# FA_2021_PCB.net
KiCad netlist of a schematic drawn in EAGLE
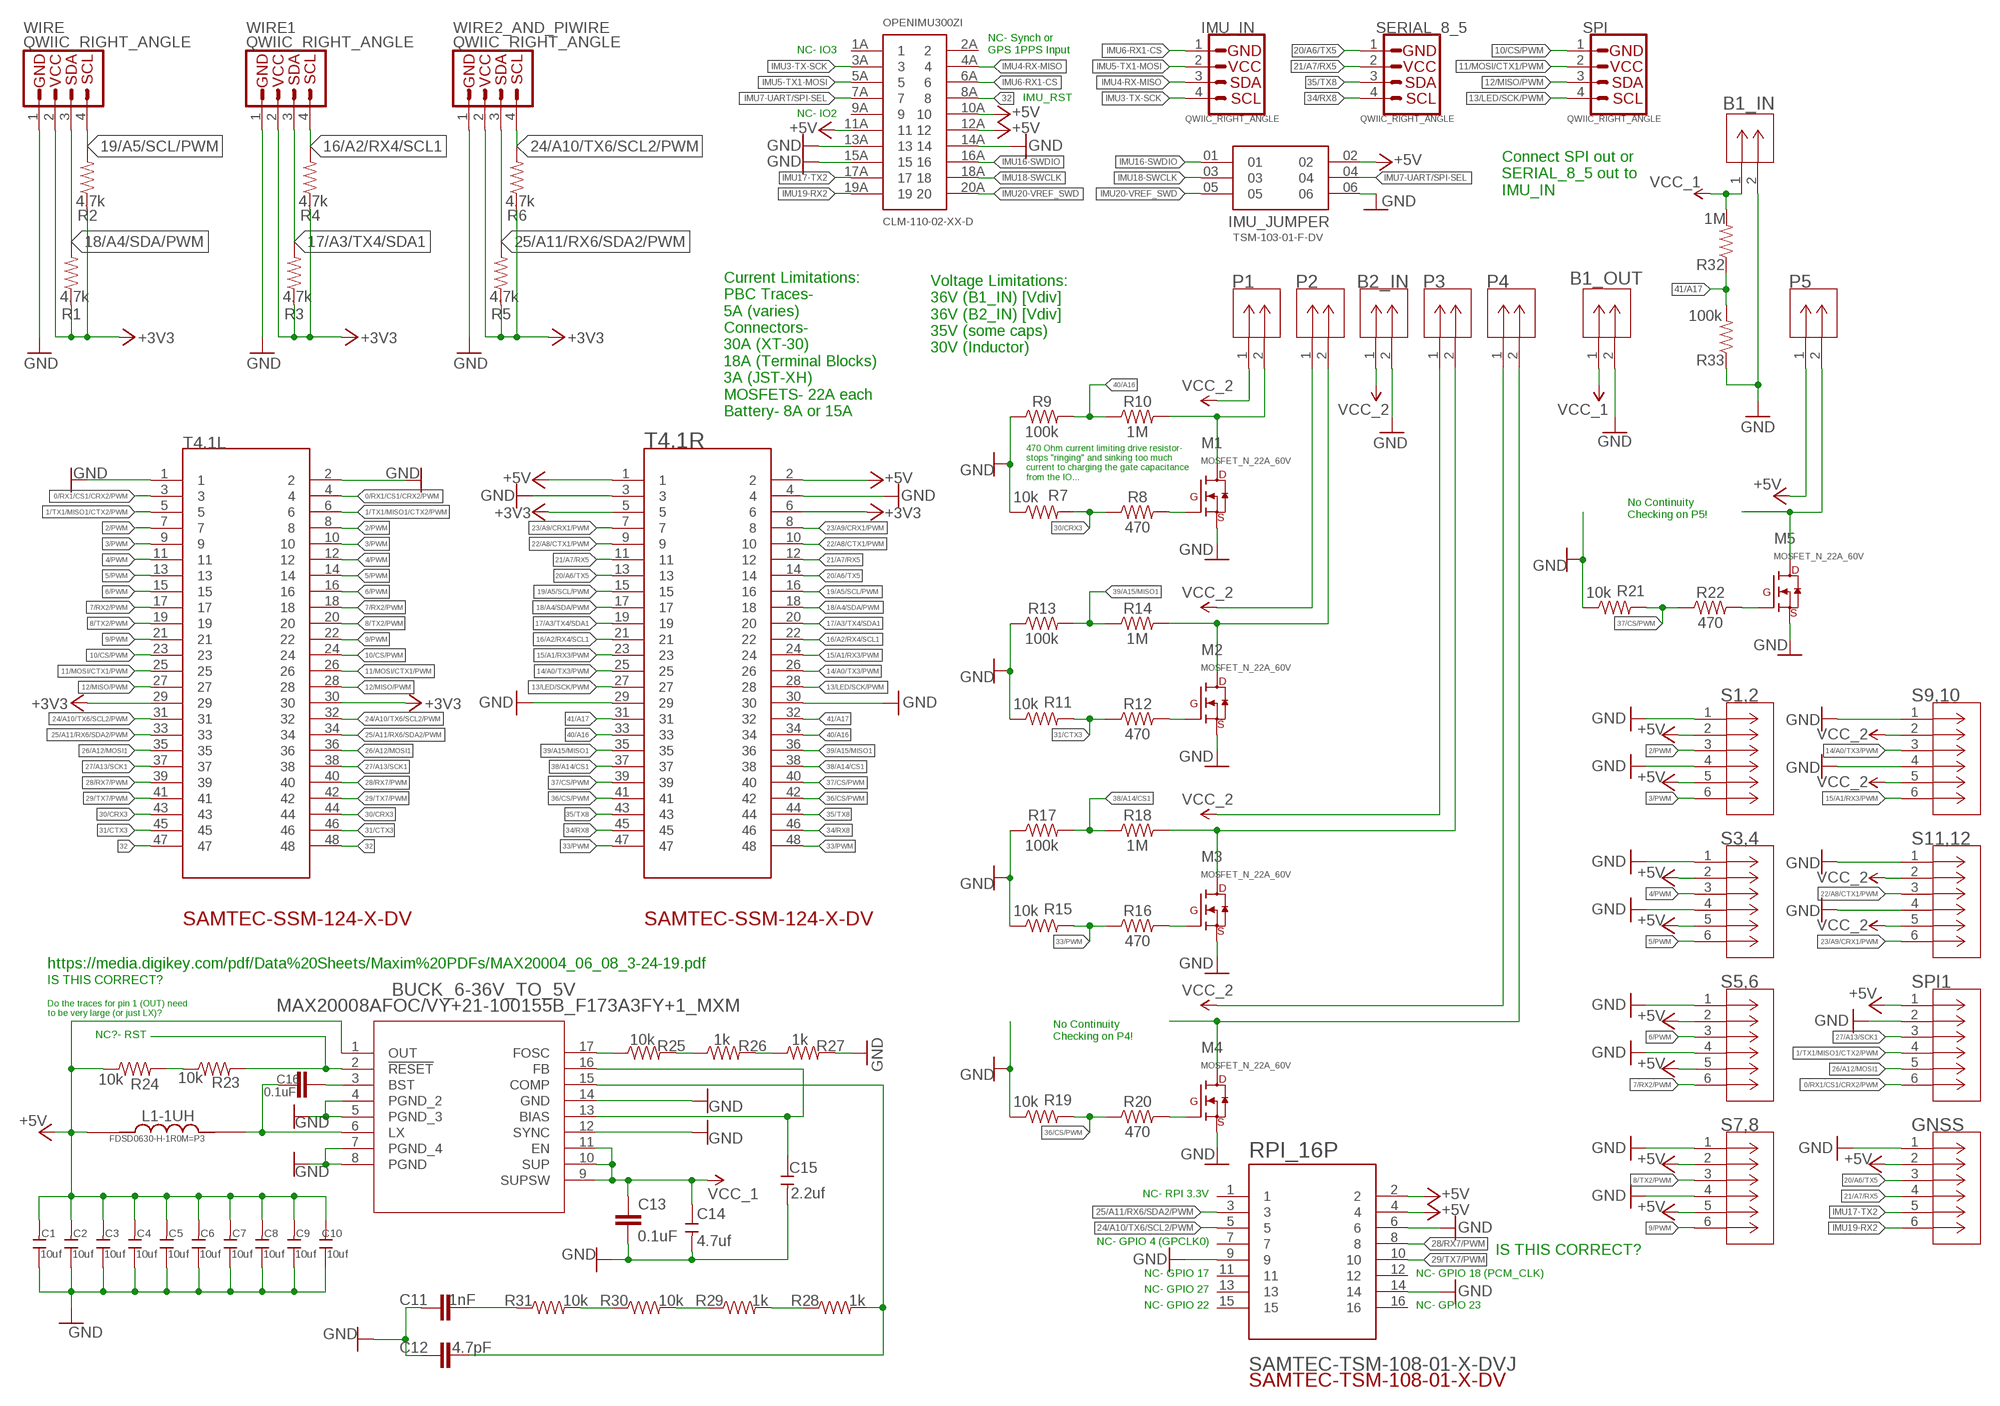
[diagram p0: schematic, sheet 1]

(export (version "E")
  (design (tool "Eeschema 10.0.6"))
  (components
    (comp (ref "B1_IN")
      (value "TERMINAL_BLOCK_2P_5MMCONN_1935161_PXC")
      (footprint "eagle-import:CONN_1935161_PXC")
      (fields
        (field (name "MANUFACTURER_PART_NUMBER") "1935161")
        (field (name "COPYRIGHT") "Copyright (C) 2018 Accelerated Designs. All rights reserved")
      )
      (libsource (lib "eagle-import") (part "TERMINAL_BLOCK_2P_5MMCONN_1935161_PXC"))
    )
    (comp (ref "B1_OUT")
      (value "TERMINAL_BLOCK_2P_5MMCONN_1935161_PXC")
      (footprint "eagle-import:CONN_1935161_PXC")
      (fields
        (field (name "MANUFACTURER_PART_NUMBER") "1935161")
        (field (name "COPYRIGHT") "Copyright (C) 2018 Accelerated Designs. All rights reserved")
      )
      (libsource (lib "eagle-import") (part "TERMINAL_BLOCK_2P_5MMCONN_1935161_PXC"))
    )
    (comp (ref "B2_IN")
      (value "TERMINAL_BLOCK_2P_5MMCONN_1935161_PXC")
      (footprint "eagle-import:CONN_1935161_PXC")
      (fields
        (field (name "MANUFACTURER_PART_NUMBER") "1935161")
        (field (name "COPYRIGHT") "Copyright (C) 2018 Accelerated Designs. All rights reserved")
      )
      (libsource (lib "eagle-import") (part "TERMINAL_BLOCK_2P_5MMCONN_1935161_PXC"))
    )
    (comp (ref "BUCK_6-36V_TO_5V")
      (value "MAX20008AFOC/VY+21-100155B_F173A3FY+1_MXM")
      (footprint "eagle-import:21-100155B_F173A3FY+1_MXM")
      (fields
        (field (name "MANUFACTURER_PART_NUMBER") "MAX20008AFOC/VY+")
        (field (name "COPYRIGHT") "Copyright (C) 2018 Accelerated Designs. All rights reserved")
      )
      (libsource (lib "eagle-import") (part "MAX20008AFOC/VY+21-100155B_F173A3FY+1_MXM"))
    )
    (comp (ref "C1")
      (value "10uf")
      (footprint "eagle-import:C1206")
      (fields (field (name "MPN") "CC1206KKX5R8BB106"))
      (libsource (lib "eagle-import") (part "CERAMIC-10UF-25V-10%-X5R(1206)"))
    )
    (comp (ref "C2")
      (value "10uf")
      (footprint "eagle-import:C1206")
      (fields (field (name "MPN") "CC1206KKX5R8BB106"))
      (libsource (lib "eagle-import") (part "CERAMIC-10UF-25V-10%-X5R(1206)"))
    )
    (comp (ref "C3")
      (value "10uf")
      (footprint "eagle-import:C1206")
      (fields (field (name "MPN") "CC1206KKX5R8BB106"))
      (libsource (lib "eagle-import") (part "CERAMIC-10UF-25V-10%-X5R(1206)"))
    )
    (comp (ref "C4")
      (value "10uf")
      (footprint "eagle-import:C1206")
      (fields (field (name "MPN") "CC1206KKX5R8BB106"))
      (libsource (lib "eagle-import") (part "CERAMIC-10UF-25V-10%-X5R(1206)"))
    )
    (comp (ref "C5")
      (value "10uf")
      (footprint "eagle-import:C1206")
      (fields (field (name "MPN") "CC1206KKX5R8BB106"))
      (libsource (lib "eagle-import") (part "CERAMIC-10UF-25V-10%-X5R(1206)"))
    )
    (comp (ref "C6")
      (value "10uf")
      (footprint "eagle-import:C1206")
      (fields (field (name "MPN") "CC1206KKX5R8BB106"))
      (libsource (lib "eagle-import") (part "CERAMIC-10UF-25V-10%-X5R(1206)"))
    )
    (comp (ref "C7")
      (value "10uf")
      (footprint "eagle-import:C1206")
      (fields (field (name "MPN") "CC1206KKX5R8BB106"))
      (libsource (lib "eagle-import") (part "CERAMIC-10UF-25V-10%-X5R(1206)"))
    )
    (comp (ref "C8")
      (value "10uf")
      (footprint "eagle-import:C1206")
      (fields (field (name "MPN") "CC1206KKX5R8BB106"))
      (libsource (lib "eagle-import") (part "CERAMIC-10UF-25V-10%-X5R(1206)"))
    )
    (comp (ref "C9")
      (value "10uf")
      (footprint "eagle-import:C1206")
      (fields (field (name "MPN") "CC1206KKX5R8BB106"))
      (libsource (lib "eagle-import") (part "CERAMIC-10UF-25V-10%-X5R(1206)"))
    )
    (comp (ref "C10")
      (value "10uf")
      (footprint "eagle-import:C1206")
      (fields (field (name "MPN") "CC1206KKX5R8BB106"))
      (libsource (lib "eagle-import") (part "CERAMIC-10UF-25V-10%-X5R(1206)"))
    )
    (comp (ref "C11")
      (value "1nF")
      (footprint "eagle-import:0603")
      (libsource (lib "eagle-import") (part "1.0NF/1000PF-0603-50V-10%"))
    )
    (comp (ref "C12")
      (value "4.7pF")
      (footprint "eagle-import:0603")
      (libsource (lib "eagle-import") (part "4.7PF-0603-50V-5%"))
    )
    (comp (ref "C13")
      (value "0.1uF")
      (footprint "eagle-import:0603")
      (libsource (lib "eagle-import") (part "0.1UF-0603-100V-10%"))
    )
    (comp (ref "C14")
      (value "4.7uf")
      (footprint "eagle-import:C0805")
      (fields (field (name "MPN") "CC0805KKX5R8BB475"))
      (libsource (lib "eagle-import") (part "CERAMIC-4.7UF-25V-10%-X5R(0805)"))
    )
    (comp (ref "C15")
      (value "2.2uf")
      (footprint "eagle-import:C0805")
      (fields (field (name "MPN") "CC0805KKX7R8BB225"))
      (libsource (lib "eagle-import") (part "CERAMIC-2.2UF-25V-10%-X7R(0805)"))
    )
    (comp (ref "C16")
      (value "0.1uF")
      (footprint "eagle-import:0603")
      (libsource (lib "eagle-import") (part "0.1UF-0603-100V-10%"))
    )
    (comp (ref "GNSS")
      (value "S6B-XH-SM4-TB(LF)(SN)CONN_S6B-XH-SM4-TB_JST")
      (footprint "eagle-import:CONN_S6B-XH-SM4-TB_JST")
      (fields
        (field (name "MANUFACTURER_PART_NUMBER") "S6B-XH-SM4-TB(LF)(SN)")
        (field (name "COPYRIGHT") "Copyright (C) 2018 Accelerated Designs. All rights reserved")
      )
      (libsource (lib "eagle-import") (part "S6B-XH-SM4-TB(LF)(SN)CONN_S6B-XH-SM4-TB_JST"))
    )
    (comp (ref "IMU_IN")
      (value "QWIIC_RIGHT_ANGLE")
      (footprint "eagle-import:JST04_1MM_RA")
      (libsource (lib "eagle-import") (part "QWIIC_CONNECTORJS-1MM"))
    )
    (comp (ref "IMU_JUMPER")
      (value "TSM-103-01-F-DV")
      (footprint "eagle-import:SAMTEC_TSM-103-01-F-DV")
      (fields (field (name "MANUFACTURER") "SAMTEC "))
      (libsource (lib "eagle-import") (part "TSM-103-01-F-DV"))
    )
    (comp (ref "L1-1UH")
      (value "FDSD0630-H-1R0M=P3")
      (footprint "eagle-import:IND_FDSD0630-H-1R0M=P3")
      (fields (field (name "DIGI-KEY_PART_NUMBER") "490-10878-1-ND") (field (name "MF") "Murata"))
      (libsource (lib "eagle-import") (part "FDSD0630-H-1R0M=P3"))
    )
    (comp (ref "M1")
      (value "MOSFET_N_22A_60V")
      (footprint "eagle-import:SOT-669_LFPAK56_POWERSO8")
      (libsource (lib "eagle-import") (part "MOSFET_N_22A_60V"))
    )
    (comp (ref "M2")
      (value "MOSFET_N_22A_60V")
      (footprint "eagle-import:SOT-669_LFPAK56_POWERSO8")
      (libsource (lib "eagle-import") (part "MOSFET_N_22A_60V"))
    )
    (comp (ref "M3")
      (value "MOSFET_N_22A_60V")
      (footprint "eagle-import:SOT-669_LFPAK56_POWERSO8")
      (libsource (lib "eagle-import") (part "MOSFET_N_22A_60V"))
    )
    (comp (ref "M4")
      (value "MOSFET_N_22A_60V")
      (footprint "eagle-import:SOT-669_LFPAK56_POWERSO8")
      (libsource (lib "eagle-import") (part "MOSFET_N_22A_60V"))
    )
    (comp (ref "M5")
      (value "MOSFET_N_22A_60V")
      (footprint "eagle-import:SOT-669_LFPAK56_POWERSO8")
      (libsource (lib "eagle-import") (part "MOSFET_N_22A_60V"))
    )
    (comp (ref "OPENIMU300ZI")
      (value "CLM-110-02-XX-D")
      (footprint "eagle-import:CLM-110-02-XX-D_MOD")
      (libsource (lib "eagle-import") (part "CLM-110-02-XX-D"))
    )
    (comp (ref "P1")
      (value "TERMINAL_BLOCK_2P_5MMCONN_1935161_PXC")
      (footprint "eagle-import:CONN_1935161_PXC")
      (fields
        (field (name "MANUFACTURER_PART_NUMBER") "1935161")
        (field (name "COPYRIGHT") "Copyright (C) 2018 Accelerated Designs. All rights reserved")
      )
      (libsource (lib "eagle-import") (part "TERMINAL_BLOCK_2P_5MMCONN_1935161_PXC"))
    )
    (comp (ref "P2")
      (value "TERMINAL_BLOCK_2P_5MMCONN_1935161_PXC")
      (footprint "eagle-import:CONN_1935161_PXC")
      (fields
        (field (name "MANUFACTURER_PART_NUMBER") "1935161")
        (field (name "COPYRIGHT") "Copyright (C) 2018 Accelerated Designs. All rights reserved")
      )
      (libsource (lib "eagle-import") (part "TERMINAL_BLOCK_2P_5MMCONN_1935161_PXC"))
    )
    (comp (ref "P3")
      (value "TERMINAL_BLOCK_2P_5MMCONN_1935161_PXC")
      (footprint "eagle-import:CONN_1935161_PXC")
      (fields
        (field (name "MANUFACTURER_PART_NUMBER") "1935161")
        (field (name "COPYRIGHT") "Copyright (C) 2018 Accelerated Designs. All rights reserved")
      )
      (libsource (lib "eagle-import") (part "TERMINAL_BLOCK_2P_5MMCONN_1935161_PXC"))
    )
    (comp (ref "P4")
      (value "TERMINAL_BLOCK_2P_5MMCONN_1935161_PXC")
      (footprint "eagle-import:CONN_1935161_PXC")
      (fields
        (field (name "MANUFACTURER_PART_NUMBER") "1935161")
        (field (name "COPYRIGHT") "Copyright (C) 2018 Accelerated Designs. All rights reserved")
      )
      (libsource (lib "eagle-import") (part "TERMINAL_BLOCK_2P_5MMCONN_1935161_PXC"))
    )
    (comp (ref "P5")
      (value "TERMINAL_BLOCK_2P_5MMCONN_1935161_PXC")
      (footprint "eagle-import:CONN_1935161_PXC")
      (fields
        (field (name "MANUFACTURER_PART_NUMBER") "1935161")
        (field (name "COPYRIGHT") "Copyright (C) 2018 Accelerated Designs. All rights reserved")
      )
      (libsource (lib "eagle-import") (part "TERMINAL_BLOCK_2P_5MMCONN_1935161_PXC"))
    )
    (comp (ref "R1")
      (value "4.7k")
      (footprint "eagle-import:0603")
      (libsource (lib "eagle-import") (part "4.7KOHM-0603-1/10W-1%"))
    )
    (comp (ref "R2")
      (value "4.7k")
      (footprint "eagle-import:0603")
      (libsource (lib "eagle-import") (part "4.7KOHM-0603-1/10W-1%"))
    )
    (comp (ref "R3")
      (value "4.7k")
      (footprint "eagle-import:0603")
      (libsource (lib "eagle-import") (part "4.7KOHM-0603-1/10W-1%"))
    )
    (comp (ref "R4")
      (value "4.7k")
      (footprint "eagle-import:0603")
      (libsource (lib "eagle-import") (part "4.7KOHM-0603-1/10W-1%"))
    )
    (comp (ref "R5")
      (value "4.7k")
      (footprint "eagle-import:0603")
      (libsource (lib "eagle-import") (part "4.7KOHM-0603-1/10W-1%"))
    )
    (comp (ref "R6")
      (value "4.7k")
      (footprint "eagle-import:0603")
      (libsource (lib "eagle-import") (part "4.7KOHM-0603-1/10W-1%"))
    )
    (comp (ref "R7")
      (value "10k")
      (footprint "eagle-import:0603")
      (libsource (lib "eagle-import") (part "10KOHM-0603-1/10W-1%"))
    )
    (comp (ref "R8")
      (value "470")
      (footprint "eagle-import:0603")
      (libsource (lib "eagle-import") (part "470OHM-0603-1/10W-1%"))
    )
    (comp (ref "R9")
      (value "100k")
      (footprint "eagle-import:0603")
      (libsource (lib "eagle-import") (part "100KOHM-0603-1/10W-1%"))
    )
    (comp (ref "R10")
      (value "1M")
      (footprint "eagle-import:0603")
      (libsource (lib "eagle-import") (part "1MOHM-0603-1/4W-5%"))
    )
    (comp (ref "R11")
      (value "10k")
      (footprint "eagle-import:0603")
      (libsource (lib "eagle-import") (part "10KOHM-0603-1/10W-1%"))
    )
    (comp (ref "R12")
      (value "470")
      (footprint "eagle-import:0603")
      (libsource (lib "eagle-import") (part "470OHM-0603-1/10W-1%"))
    )
    (comp (ref "R13")
      (value "100k")
      (footprint "eagle-import:0603")
      (libsource (lib "eagle-import") (part "100KOHM-0603-1/10W-1%"))
    )
    (comp (ref "R14")
      (value "1M")
      (footprint "eagle-import:0603")
      (libsource (lib "eagle-import") (part "1MOHM-0603-1/4W-5%"))
    )
    (comp (ref "R15")
      (value "10k")
      (footprint "eagle-import:0603")
      (libsource (lib "eagle-import") (part "10KOHM-0603-1/10W-1%"))
    )
    (comp (ref "R16")
      (value "470")
      (footprint "eagle-import:0603")
      (libsource (lib "eagle-import") (part "470OHM-0603-1/10W-1%"))
    )
    (comp (ref "R17")
      (value "100k")
      (footprint "eagle-import:0603")
      (libsource (lib "eagle-import") (part "100KOHM-0603-1/10W-1%"))
    )
    (comp (ref "R18")
      (value "1M")
      (footprint "eagle-import:0603")
      (libsource (lib "eagle-import") (part "1MOHM-0603-1/4W-5%"))
    )
    (comp (ref "R19")
      (value "10k")
      (footprint "eagle-import:0603")
      (libsource (lib "eagle-import") (part "10KOHM-0603-1/10W-1%"))
    )
    (comp (ref "R20")
      (value "470")
      (footprint "eagle-import:0603")
      (libsource (lib "eagle-import") (part "470OHM-0603-1/10W-1%"))
    )
    (comp (ref "R21")
      (value "10k")
      (footprint "eagle-import:0603")
      (libsource (lib "eagle-import") (part "10KOHM-0603-1/10W-1%"))
    )
    (comp (ref "R22")
      (value "470")
      (footprint "eagle-import:0603")
      (libsource (lib "eagle-import") (part "470OHM-0603-1/10W-1%"))
    )
    (comp (ref "R23")
      (value "10k")
      (footprint "eagle-import:0603")
      (libsource (lib "eagle-import") (part "10KOHM-0603-1/10W-1%"))
    )
    (comp (ref "R24")
      (value "10k")
      (footprint "eagle-import:0603")
      (libsource (lib "eagle-import") (part "10KOHM-0603-1/10W-1%"))
    )
    (comp (ref "R25")
      (value "10k")
      (footprint "eagle-import:0603")
      (libsource (lib "eagle-import") (part "10KOHM-0603-1/10W-1%"))
    )
    (comp (ref "R26")
      (value "1k")
      (footprint "eagle-import:0603")
      (libsource (lib "eagle-import") (part "1KOHM-0603-1/10W-1%"))
    )
    (comp (ref "R27")
      (value "1k")
      (footprint "eagle-import:0603")
      (libsource (lib "eagle-import") (part "1KOHM-0603-1/10W-1%"))
    )
    (comp (ref "R28")
      (value "1k")
      (footprint "eagle-import:0603")
      (libsource (lib "eagle-import") (part "1KOHM-0603-1/10W-1%"))
    )
    (comp (ref "R29")
      (value "1k")
      (footprint "eagle-import:0603")
      (libsource (lib "eagle-import") (part "1KOHM-0603-1/10W-1%"))
    )
    (comp (ref "R30")
      (value "10k")
      (footprint "eagle-import:0603")
      (libsource (lib "eagle-import") (part "10KOHM-0603-1/10W-1%"))
    )
    (comp (ref "R31")
      (value "10k")
      (footprint "eagle-import:0603")
      (libsource (lib "eagle-import") (part "10KOHM-0603-1/10W-1%"))
    )
    (comp (ref "R32")
      (value "1M")
      (footprint "eagle-import:0603")
      (libsource (lib "eagle-import") (part "1MOHM-0603-1/4W-5%"))
    )
    (comp (ref "R33")
      (value "100k")
      (footprint "eagle-import:0603")
      (libsource (lib "eagle-import") (part "100KOHM-0603-1/10W-1%"))
    )
    (comp (ref "RPI_16P")
      (value "SAMTEC-TSM-108-01-X-DVJ")
      (footprint "eagle-import:SAMTEC-TSM-108-01-X-DV")
      (fields (field (name "MF") "Samtec Inc.") (field (name "MP") "TSM-108-01-T-DV"))
      (libsource (lib "eagle-import") (part "SAMTEC-TSM-108-01-X-DVJ"))
    )
    (comp (ref "S1,2")
      (value "S6B-XH-SM4-TB(LF)(SN)CONN_S6B-XH-SM4-TB_JST")
      (footprint "eagle-import:CONN_S6B-XH-SM4-TB_JST")
      (fields
        (field (name "MANUFACTURER_PART_NUMBER") "S6B-XH-SM4-TB(LF)(SN)")
        (field (name "COPYRIGHT") "Copyright (C) 2018 Accelerated Designs. All rights reserved")
      )
      (libsource (lib "eagle-import") (part "S6B-XH-SM4-TB(LF)(SN)CONN_S6B-XH-SM4-TB_JST"))
    )
    (comp (ref "S3,4")
      (value "S6B-XH-SM4-TB(LF)(SN)CONN_S6B-XH-SM4-TB_JST")
      (footprint "eagle-import:CONN_S6B-XH-SM4-TB_JST")
      (fields
        (field (name "MANUFACTURER_PART_NUMBER") "S6B-XH-SM4-TB(LF)(SN)")
        (field (name "COPYRIGHT") "Copyright (C) 2018 Accelerated Designs. All rights reserved")
      )
      (libsource (lib "eagle-import") (part "S6B-XH-SM4-TB(LF)(SN)CONN_S6B-XH-SM4-TB_JST"))
    )
    (comp (ref "S5,6")
      (value "S6B-XH-SM4-TB(LF)(SN)CONN_S6B-XH-SM4-TB_JST")
      (footprint "eagle-import:CONN_S6B-XH-SM4-TB_JST")
      (fields
        (field (name "MANUFACTURER_PART_NUMBER") "S6B-XH-SM4-TB(LF)(SN)")
        (field (name "COPYRIGHT") "Copyright (C) 2018 Accelerated Designs. All rights reserved")
      )
      (libsource (lib "eagle-import") (part "S6B-XH-SM4-TB(LF)(SN)CONN_S6B-XH-SM4-TB_JST"))
    )
    (comp (ref "S7,8")
      (value "S6B-XH-SM4-TB(LF)(SN)CONN_S6B-XH-SM4-TB_JST")
      (footprint "eagle-import:CONN_S6B-XH-SM4-TB_JST")
      (fields
        (field (name "MANUFACTURER_PART_NUMBER") "S6B-XH-SM4-TB(LF)(SN)")
        (field (name "COPYRIGHT") "Copyright (C) 2018 Accelerated Designs. All rights reserved")
      )
      (libsource (lib "eagle-import") (part "S6B-XH-SM4-TB(LF)(SN)CONN_S6B-XH-SM4-TB_JST"))
    )
    (comp (ref "S9,10")
      (value "S6B-XH-SM4-TB(LF)(SN)CONN_S6B-XH-SM4-TB_JST")
      (footprint "eagle-import:CONN_S6B-XH-SM4-TB_JST")
      (fields
        (field (name "MANUFACTURER_PART_NUMBER") "S6B-XH-SM4-TB(LF)(SN)")
        (field (name "COPYRIGHT") "Copyright (C) 2018 Accelerated Designs. All rights reserved")
      )
      (libsource (lib "eagle-import") (part "S6B-XH-SM4-TB(LF)(SN)CONN_S6B-XH-SM4-TB_JST"))
    )
    (comp (ref "S11,12")
      (value "S6B-XH-SM4-TB(LF)(SN)CONN_S6B-XH-SM4-TB_JST")
      (footprint "eagle-import:CONN_S6B-XH-SM4-TB_JST")
      (fields
        (field (name "MANUFACTURER_PART_NUMBER") "S6B-XH-SM4-TB(LF)(SN)")
        (field (name "COPYRIGHT") "Copyright (C) 2018 Accelerated Designs. All rights reserved")
      )
      (libsource (lib "eagle-import") (part "S6B-XH-SM4-TB(LF)(SN)CONN_S6B-XH-SM4-TB_JST"))
    )
    (comp (ref "SERIAL_8_5")
      (value "QWIIC_RIGHT_ANGLE")
      (footprint "eagle-import:JST04_1MM_RA")
      (libsource (lib "eagle-import") (part "QWIIC_CONNECTORJS-1MM"))
    )
    (comp (ref "SPI")
      (value "QWIIC_RIGHT_ANGLE")
      (footprint "eagle-import:JST04_1MM_RA")
      (libsource (lib "eagle-import") (part "QWIIC_CONNECTORJS-1MM"))
    )
    (comp (ref "SPI1")
      (value "S6B-XH-SM4-TB(LF)(SN)CONN_S6B-XH-SM4-TB_JST")
      (footprint "eagle-import:CONN_S6B-XH-SM4-TB_JST")
      (fields
        (field (name "MANUFACTURER_PART_NUMBER") "S6B-XH-SM4-TB(LF)(SN)")
        (field (name "COPYRIGHT") "Copyright (C) 2018 Accelerated Designs. All rights reserved")
      )
      (libsource (lib "eagle-import") (part "S6B-XH-SM4-TB(LF)(SN)CONN_S6B-XH-SM4-TB_JST"))
    )
    (comp (ref "T4.1L")
      (value "SAMTEC-SSM-124-X-DVJ")
      (footprint "eagle-import:SAMTEC-SSM-124-X-DV")
      (libsource (lib "eagle-import") (part "SAMTEC-SSM-124-X-DVJ"))
    )
    (comp (ref "T4.1R")
      (value "SAMTEC-SSM-124-X-DVJ")
      (footprint "eagle-import:SAMTEC-SSM-124-X-DV")
      (libsource (lib "eagle-import") (part "SAMTEC-SSM-124-X-DVJ"))
    )
    (comp (ref "WIRE")
      (value "QWIIC_RIGHT_ANGLE")
      (footprint "eagle-import:JST04_1MM_RA")
      (libsource (lib "eagle-import") (part "QWIIC_CONNECTORJS-1MM"))
    )
    (comp (ref "WIRE1")
      (value "QWIIC_RIGHT_ANGLE")
      (footprint "eagle-import:JST04_1MM_RA")
      (libsource (lib "eagle-import") (part "QWIIC_CONNECTORJS-1MM"))
    )
    (comp (ref "WIRE2_AND_PIWIRE")
      (value "QWIIC_RIGHT_ANGLE")
      (footprint "eagle-import:JST04_1MM_RA")
      (libsource (lib "eagle-import") (part "QWIIC_CONNECTORJS-1MM"))
    )
  )
  (nets
    (net (code "1") (name "+3V3") (class "Default")
      (node (ref "R1") (pin "1") (pinfunction "1_1") (pintype "passive"))
      (node (ref "R2") (pin "1") (pinfunction "1_1") (pintype "passive"))
      (node (ref "R3") (pin "1") (pinfunction "1_1") (pintype "passive"))
      (node (ref "R4") (pin "1") (pinfunction "1_1") (pintype "passive"))
      (node (ref "R5") (pin "1") (pinfunction "1_1") (pintype "passive"))
      (node (ref "R6") (pin "1") (pinfunction "1_1") (pintype "passive"))
      (node (ref "T4.1L") (pin "29") (pinfunction "29_29") (pintype "passive"))
      (node (ref "T4.1L") (pin "30") (pinfunction "30_30") (pintype "passive"))
      (node (ref "T4.1R") (pin "5") (pinfunction "5_5") (pintype "passive"))
      (node (ref "T4.1R") (pin "6") (pinfunction "6_6") (pintype "passive"))
      (node (ref "WIRE") (pin "2") (pinfunction "2_2") (pintype "power_in"))
      (node (ref "WIRE1") (pin "2") (pinfunction "2_2") (pintype "power_in"))
      (node (ref "WIRE2_AND_PIWIRE") (pin "2") (pinfunction "2_2") (pintype "power_in"))
    )
    (net (code "2") (name "+5V") (class "Default")
      (node (ref "BUCK_6-36V_TO_5V") (pin "1") (pinfunction "OUT_1") (pintype "output"))
      (node (ref "C1") (pin "2") (pinfunction "2_2") (pintype "passive"))
      (node (ref "C10") (pin "2") (pinfunction "2_2") (pintype "passive"))
      (node (ref "C2") (pin "2") (pinfunction "2_2") (pintype "passive"))
      (node (ref "C3") (pin "2") (pinfunction "2_2") (pintype "passive"))
      (node (ref "C4") (pin "2") (pinfunction "2_2") (pintype "passive"))
      (node (ref "C5") (pin "2") (pinfunction "2_2") (pintype "passive"))
      (node (ref "C6") (pin "2") (pinfunction "2_2") (pintype "passive"))
      (node (ref "C7") (pin "2") (pinfunction "2_2") (pintype "passive"))
      (node (ref "C8") (pin "2") (pinfunction "2_2") (pintype "passive"))
      (node (ref "C9") (pin "2") (pinfunction "2_2") (pintype "passive"))
      (node (ref "GNSS") (pin "2") (pinfunction "2_2") (pintype "passive"))
      (node (ref "IMU_JUMPER") (pin "02") (pinfunction "02_02") (pintype "passive"))
      (node (ref "L1-1UH") (pin "1") (pinfunction "1_1") (pintype "passive"))
      (node (ref "OPENIMU300ZI") (pin "10A") (pinfunction "10_10A") (pintype "bidirectional"))
      (node (ref "OPENIMU300ZI") (pin "11A") (pinfunction "11_11A") (pintype "bidirectional"))
      (node (ref "OPENIMU300ZI") (pin "12A") (pinfunction "12_12A") (pintype "bidirectional"))
      (node (ref "P5") (pin "1") (pinfunction "1_1") (pintype "passive"))
      (node (ref "R24") (pin "1") (pinfunction "1_1") (pintype "passive"))
      (node (ref "RPI_16P") (pin "2") (pinfunction "2_2") (pintype "passive"))
      (node (ref "RPI_16P") (pin "4") (pinfunction "4_4") (pintype "passive"))
      (node (ref "S1,2") (pin "2") (pinfunction "2_2") (pintype "passive"))
      (node (ref "S1,2") (pin "5") (pinfunction "5_5") (pintype "passive"))
      (node (ref "S3,4") (pin "2") (pinfunction "2_2") (pintype "passive"))
      (node (ref "S3,4") (pin "5") (pinfunction "5_5") (pintype "passive"))
      (node (ref "S5,6") (pin "2") (pinfunction "2_2") (pintype "passive"))
      (node (ref "S5,6") (pin "5") (pinfunction "5_5") (pintype "passive"))
      (node (ref "S7,8") (pin "2") (pinfunction "2_2") (pintype "passive"))
      (node (ref "S7,8") (pin "5") (pinfunction "5_5") (pintype "passive"))
      (node (ref "SPI1") (pin "1") (pinfunction "1_1") (pintype "passive"))
      (node (ref "T4.1R") (pin "1") (pinfunction "1_1") (pintype "passive"))
      (node (ref "T4.1R") (pin "2") (pinfunction "2_2") (pintype "passive"))
    )
    (net (code "3") (name "0{slash}RX1{slash}CS1{slash}CRX2{slash}PWM") (class "Default")
      (node (ref "SPI1") (pin "6") (pinfunction "6_6") (pintype "passive"))
      (node (ref "T4.1L") (pin "3") (pinfunction "3_3") (pintype "passive"))
      (node (ref "T4.1L") (pin "4") (pinfunction "4_4") (pintype "passive"))
    )
    (net (code "4") (name "1{slash}TX1{slash}MISO1{slash}CTX2{slash}PWM") (class "Default")
      (node (ref "SPI1") (pin "4") (pinfunction "4_4") (pintype "passive"))
      (node (ref "T4.1L") (pin "5") (pinfunction "5_5") (pintype "passive"))
      (node (ref "T4.1L") (pin "6") (pinfunction "6_6") (pintype "passive"))
    )
    (net (code "5") (name "2{slash}PWM") (class "Default")
      (node (ref "S1,2") (pin "3") (pinfunction "3_3") (pintype "passive"))
      (node (ref "T4.1L") (pin "7") (pinfunction "7_7") (pintype "passive"))
      (node (ref "T4.1L") (pin "8") (pinfunction "8_8") (pintype "passive"))
    )
    (net (code "6") (name "3{slash}PWM") (class "Default")
      (node (ref "S1,2") (pin "6") (pinfunction "6_6") (pintype "passive"))
      (node (ref "T4.1L") (pin "10") (pinfunction "10_10") (pintype "passive"))
      (node (ref "T4.1L") (pin "9") (pinfunction "9_9") (pintype "passive"))
    )
    (net (code "7") (name "4{slash}PWM") (class "Default")
      (node (ref "S3,4") (pin "3") (pinfunction "3_3") (pintype "passive"))
      (node (ref "T4.1L") (pin "11") (pinfunction "11_11") (pintype "passive"))
      (node (ref "T4.1L") (pin "12") (pinfunction "12_12") (pintype "passive"))
    )
    (net (code "8") (name "5{slash}PWM") (class "Default")
      (node (ref "S3,4") (pin "6") (pinfunction "6_6") (pintype "passive"))
      (node (ref "T4.1L") (pin "13") (pinfunction "13_13") (pintype "passive"))
      (node (ref "T4.1L") (pin "14") (pinfunction "14_14") (pintype "passive"))
    )
    (net (code "9") (name "6{slash}PWM") (class "Default")
      (node (ref "S5,6") (pin "3") (pinfunction "3_3") (pintype "passive"))
      (node (ref "T4.1L") (pin "15") (pinfunction "15_15") (pintype "passive"))
      (node (ref "T4.1L") (pin "16") (pinfunction "16_16") (pintype "passive"))
    )
    (net (code "10") (name "7{slash}RX2{slash}PWM") (class "Default")
      (node (ref "S5,6") (pin "6") (pinfunction "6_6") (pintype "passive"))
      (node (ref "T4.1L") (pin "17") (pinfunction "17_17") (pintype "passive"))
      (node (ref "T4.1L") (pin "18") (pinfunction "18_18") (pintype "passive"))
    )
    (net (code "11") (name "8{slash}TX2{slash}PWM") (class "Default")
      (node (ref "S7,8") (pin "3") (pinfunction "3_3") (pintype "passive"))
      (node (ref "T4.1L") (pin "19") (pinfunction "19_19") (pintype "passive"))
      (node (ref "T4.1L") (pin "20") (pinfunction "20_20") (pintype "passive"))
    )
    (net (code "12") (name "9{slash}PWM") (class "Default")
      (node (ref "S7,8") (pin "6") (pinfunction "6_6") (pintype "passive"))
      (node (ref "T4.1L") (pin "21") (pinfunction "21_21") (pintype "passive"))
      (node (ref "T4.1L") (pin "22") (pinfunction "22_22") (pintype "passive"))
    )
    (net (code "13") (name "10{slash}CS{slash}PWM") (class "Default")
      (node (ref "SPI") (pin "1") (pinfunction "1_1") (pintype "power_in"))
      (node (ref "T4.1L") (pin "23") (pinfunction "23_23") (pintype "passive"))
      (node (ref "T4.1L") (pin "24") (pinfunction "24_24") (pintype "passive"))
    )
    (net (code "14") (name "11{slash}MOSI{slash}CTX1{slash}PWM") (class "Default")
      (node (ref "SPI") (pin "2") (pinfunction "2_2") (pintype "power_in"))
      (node (ref "T4.1L") (pin "25") (pinfunction "25_25") (pintype "passive"))
      (node (ref "T4.1L") (pin "26") (pinfunction "26_26") (pintype "passive"))
    )
    (net (code "15") (name "12{slash}MISO{slash}PWM") (class "Default")
      (node (ref "SPI") (pin "3") (pinfunction "3_3") (pintype "passive"))
      (node (ref "T4.1L") (pin "27") (pinfunction "27_27") (pintype "passive"))
      (node (ref "T4.1L") (pin "28") (pinfunction "28_28") (pintype "passive"))
    )
    (net (code "16") (name "13{slash}LED{slash}SCK{slash}PWM") (class "Default")
      (node (ref "SPI") (pin "4") (pinfunction "4_4") (pintype "passive"))
      (node (ref "T4.1R") (pin "27") (pinfunction "27_27") (pintype "passive"))
      (node (ref "T4.1R") (pin "28") (pinfunction "28_28") (pintype "passive"))
    )
    (net (code "17") (name "14{slash}A0{slash}TX3{slash}PWM") (class "Default")
      (node (ref "S9,10") (pin "3") (pinfunction "3_3") (pintype "passive"))
      (node (ref "T4.1R") (pin "25") (pinfunction "25_25") (pintype "passive"))
      (node (ref "T4.1R") (pin "26") (pinfunction "26_26") (pintype "passive"))
    )
    (net (code "18") (name "15{slash}A1{slash}RX3{slash}PWM") (class "Default")
      (node (ref "S9,10") (pin "6") (pinfunction "6_6") (pintype "passive"))
      (node (ref "T4.1R") (pin "23") (pinfunction "23_23") (pintype "passive"))
      (node (ref "T4.1R") (pin "24") (pinfunction "24_24") (pintype "passive"))
    )
    (net (code "19") (name "16{slash}A2{slash}RX4{slash}SCL1") (class "Default")
      (node (ref "R4") (pin "2") (pinfunction "2_2") (pintype "passive"))
      (node (ref "T4.1R") (pin "21") (pinfunction "21_21") (pintype "passive"))
      (node (ref "T4.1R") (pin "22") (pinfunction "22_22") (pintype "passive"))
      (node (ref "WIRE1") (pin "4") (pinfunction "4_4") (pintype "passive"))
    )
    (net (code "20") (name "17{slash}A3{slash}TX4{slash}SDA1") (class "Default")
      (node (ref "R3") (pin "2") (pinfunction "2_2") (pintype "passive"))
      (node (ref "T4.1R") (pin "19") (pinfunction "19_19") (pintype "passive"))
      (node (ref "T4.1R") (pin "20") (pinfunction "20_20") (pintype "passive"))
      (node (ref "WIRE1") (pin "3") (pinfunction "3_3") (pintype "passive"))
    )
    (net (code "21") (name "18{slash}A4{slash}SDA{slash}PWM") (class "Default")
      (node (ref "R1") (pin "2") (pinfunction "2_2") (pintype "passive"))
      (node (ref "T4.1R") (pin "17") (pinfunction "17_17") (pintype "passive"))
      (node (ref "T4.1R") (pin "18") (pinfunction "18_18") (pintype "passive"))
      (node (ref "WIRE") (pin "3") (pinfunction "3_3") (pintype "passive"))
    )
    (net (code "22") (name "19{slash}A5{slash}SCL{slash}PWM") (class "Default")
      (node (ref "R2") (pin "2") (pinfunction "2_2") (pintype "passive"))
      (node (ref "T4.1R") (pin "15") (pinfunction "15_15") (pintype "passive"))
      (node (ref "T4.1R") (pin "16") (pinfunction "16_16") (pintype "passive"))
      (node (ref "WIRE") (pin "4") (pinfunction "4_4") (pintype "passive"))
    )
    (net (code "23") (name "20{slash}A6{slash}TX5") (class "Default")
      (node (ref "GNSS") (pin "3") (pinfunction "3_3") (pintype "passive"))
      (node (ref "SERIAL_8_5") (pin "1") (pinfunction "1_1") (pintype "power_in"))
      (node (ref "T4.1R") (pin "13") (pinfunction "13_13") (pintype "passive"))
      (node (ref "T4.1R") (pin "14") (pinfunction "14_14") (pintype "passive"))
    )
    (net (code "24") (name "21{slash}A7{slash}RX5") (class "Default")
      (node (ref "GNSS") (pin "4") (pinfunction "4_4") (pintype "passive"))
      (node (ref "SERIAL_8_5") (pin "2") (pinfunction "2_2") (pintype "power_in"))
      (node (ref "T4.1R") (pin "11") (pinfunction "11_11") (pintype "passive"))
      (node (ref "T4.1R") (pin "12") (pinfunction "12_12") (pintype "passive"))
    )
    (net (code "25") (name "22{slash}A8{slash}CTX1{slash}PWM") (class "Default")
      (node (ref "S11,12") (pin "3") (pinfunction "3_3") (pintype "passive"))
      (node (ref "T4.1R") (pin "10") (pinfunction "10_10") (pintype "passive"))
      (node (ref "T4.1R") (pin "9") (pinfunction "9_9") (pintype "passive"))
    )
    (net (code "26") (name "23{slash}A9{slash}CRX1{slash}PWM") (class "Default")
      (node (ref "S11,12") (pin "6") (pinfunction "6_6") (pintype "passive"))
      (node (ref "T4.1R") (pin "7") (pinfunction "7_7") (pintype "passive"))
      (node (ref "T4.1R") (pin "8") (pinfunction "8_8") (pintype "passive"))
    )
    (net (code "27") (name "24{slash}A10{slash}TX6{slash}SCL2{slash}PWM") (class "Default")
      (node (ref "R6") (pin "2") (pinfunction "2_2") (pintype "passive"))
      (node (ref "RPI_16P") (pin "5") (pinfunction "5_5") (pintype "passive"))
      (node (ref "T4.1L") (pin "31") (pinfunction "31_31") (pintype "passive"))
      (node (ref "T4.1L") (pin "32") (pinfunction "32_32") (pintype "passive"))
      (node (ref "WIRE2_AND_PIWIRE") (pin "4") (pinfunction "4_4") (pintype "passive"))
    )
    (net (code "28") (name "25{slash}A11{slash}RX6{slash}SDA2{slash}PWM") (class "Default")
      (node (ref "R5") (pin "2") (pinfunction "2_2") (pintype "passive"))
      (node (ref "RPI_16P") (pin "3") (pinfunction "3_3") (pintype "passive"))
      (node (ref "T4.1L") (pin "33") (pinfunction "33_33") (pintype "passive"))
      (node (ref "T4.1L") (pin "34") (pinfunction "34_34") (pintype "passive"))
      (node (ref "WIRE2_AND_PIWIRE") (pin "3") (pinfunction "3_3") (pintype "passive"))
    )
    (net (code "29") (name "26{slash}A12{slash}MOSI1") (class "Default")
      (node (ref "SPI1") (pin "5") (pinfunction "5_5") (pintype "passive"))
      (node (ref "T4.1L") (pin "35") (pinfunction "35_35") (pintype "passive"))
      (node (ref "T4.1L") (pin "36") (pinfunction "36_36") (pintype "passive"))
    )
    (net (code "30") (name "27{slash}A13{slash}SCK1") (class "Default")
      (node (ref "SPI1") (pin "3") (pinfunction "3_3") (pintype "passive"))
      (node (ref "T4.1L") (pin "37") (pinfunction "37_37") (pintype "passive"))
      (node (ref "T4.1L") (pin "38") (pinfunction "38_38") (pintype "passive"))
    )
    (net (code "31") (name "28{slash}RX7{slash}PWM") (class "Default")
      (node (ref "RPI_16P") (pin "8") (pinfunction "8_8") (pintype "passive"))
      (node (ref "T4.1L") (pin "39") (pinfunction "39_39") (pintype "passive"))
      (node (ref "T4.1L") (pin "40") (pinfunction "40_40") (pintype "passive"))
    )
    (net (code "32") (name "29{slash}TX7{slash}PWM") (class "Default")
      (node (ref "RPI_16P") (pin "10") (pinfunction "10_10") (pintype "passive"))
      (node (ref "T4.1L") (pin "41") (pinfunction "41_41") (pintype "passive"))
      (node (ref "T4.1L") (pin "42") (pinfunction "42_42") (pintype "passive"))
    )
    (net (code "33") (name "30{slash}CRX3") (class "Default")
      (node (ref "R7") (pin "2") (pinfunction "2_2") (pintype "passive"))
      (node (ref "R8") (pin "1") (pinfunction "1_1") (pintype "passive"))
      (node (ref "T4.1L") (pin "43") (pinfunction "43_43") (pintype "passive"))
      (node (ref "T4.1L") (pin "44") (pinfunction "44_44") (pintype "passive"))
    )
    (net (code "34") (name "31{slash}CTX3") (class "Default")
      (node (ref "R11") (pin "2") (pinfunction "2_2") (pintype "passive"))
      (node (ref "R12") (pin "1") (pinfunction "1_1") (pintype "passive"))
      (node (ref "T4.1L") (pin "45") (pinfunction "45_45") (pintype "passive"))
      (node (ref "T4.1L") (pin "46") (pinfunction "46_46") (pintype "passive"))
    )
    (net (code "35") (name "32") (class "Default")
      (node (ref "OPENIMU300ZI") (pin "8A") (pinfunction "8_8A") (pintype "bidirectional"))
      (node (ref "T4.1L") (pin "47") (pinfunction "47_47") (pintype "passive"))
      (node (ref "T4.1L") (pin "48") (pinfunction "48_48") (pintype "passive"))
    )
    (net (code "36") (name "33{slash}PWM") (class "Default")
      (node (ref "R15") (pin "2") (pinfunction "2_2") (pintype "passive"))
      (node (ref "R16") (pin "1") (pinfunction "1_1") (pintype "passive"))
      (node (ref "T4.1R") (pin "47") (pinfunction "47_47") (pintype "passive"))
      (node (ref "T4.1R") (pin "48") (pinfunction "48_48") (pintype "passive"))
    )
    (net (code "37") (name "34{slash}RX8") (class "Default")
      (node (ref "SERIAL_8_5") (pin "4") (pinfunction "4_4") (pintype "passive"))
      (node (ref "T4.1R") (pin "45") (pinfunction "45_45") (pintype "passive"))
      (node (ref "T4.1R") (pin "46") (pinfunction "46_46") (pintype "passive"))
    )
    (net (code "38") (name "35{slash}TX8") (class "Default")
      (node (ref "SERIAL_8_5") (pin "3") (pinfunction "3_3") (pintype "passive"))
      (node (ref "T4.1R") (pin "43") (pinfunction "43_43") (pintype "passive"))
      (node (ref "T4.1R") (pin "44") (pinfunction "44_44") (pintype "passive"))
    )
    (net (code "39") (name "36{slash}CS{slash}PWM") (class "Default")
      (node (ref "R19") (pin "2") (pinfunction "2_2") (pintype "passive"))
      (node (ref "R20") (pin "1") (pinfunction "1_1") (pintype "passive"))
      (node (ref "T4.1R") (pin "41") (pinfunction "41_41") (pintype "passive"))
      (node (ref "T4.1R") (pin "42") (pinfunction "42_42") (pintype "passive"))
    )
    (net (code "40") (name "37{slash}CS{slash}PWM") (class "Default")
      (node (ref "R21") (pin "2") (pinfunction "2_2") (pintype "passive"))
      (node (ref "R22") (pin "1") (pinfunction "1_1") (pintype "passive"))
      (node (ref "T4.1R") (pin "39") (pinfunction "39_39") (pintype "passive"))
      (node (ref "T4.1R") (pin "40") (pinfunction "40_40") (pintype "passive"))
    )
    (net (code "41") (name "38{slash}A14{slash}CS1") (class "Default")
      (node (ref "R17") (pin "2") (pinfunction "2_2") (pintype "passive"))
      (node (ref "R18") (pin "1") (pinfunction "1_1") (pintype "passive"))
      (node (ref "T4.1R") (pin "37") (pinfunction "37_37") (pintype "passive"))
      (node (ref "T4.1R") (pin "38") (pinfunction "38_38") (pintype "passive"))
    )
    (net (code "42") (name "39{slash}A15{slash}MISO1") (class "Default")
      (node (ref "R13") (pin "2") (pinfunction "2_2") (pintype "passive"))
      (node (ref "R14") (pin "1") (pinfunction "1_1") (pintype "passive"))
      (node (ref "T4.1R") (pin "35") (pinfunction "35_35") (pintype "passive"))
      (node (ref "T4.1R") (pin "36") (pinfunction "36_36") (pintype "passive"))
    )
    (net (code "43") (name "40{slash}A16") (class "Default")
      (node (ref "R10") (pin "1") (pinfunction "1_1") (pintype "passive"))
      (node (ref "R9") (pin "2") (pinfunction "2_2") (pintype "passive"))
      (node (ref "T4.1R") (pin "33") (pinfunction "33_33") (pintype "passive"))
      (node (ref "T4.1R") (pin "34") (pinfunction "34_34") (pintype "passive"))
    )
    (net (code "44") (name "41{slash}A17") (class "Default")
      (node (ref "R32") (pin "1") (pinfunction "1_1") (pintype "passive"))
      (node (ref "R33") (pin "2") (pinfunction "2_2") (pintype "passive"))
      (node (ref "T4.1R") (pin "31") (pinfunction "31_31") (pintype "passive"))
      (node (ref "T4.1R") (pin "32") (pinfunction "32_32") (pintype "passive"))
    )
    (net (code "45") (name "GND") (class "Default")
      (node (ref "B1_IN") (pin "2") (pinfunction "2_2") (pintype "passive"))
      (node (ref "B1_OUT") (pin "2") (pinfunction "2_2") (pintype "passive"))
      (node (ref "B2_IN") (pin "2") (pinfunction "2_2") (pintype "passive"))
      (node (ref "BUCK_6-36V_TO_5V") (pin "12") (pinfunction "SYNC_12") (pintype "passive"))
      (node (ref "BUCK_6-36V_TO_5V") (pin "14") (pinfunction "GND_14") (pintype "power_in"))
      (node (ref "BUCK_6-36V_TO_5V") (pin "4") (pinfunction "PGND_2_4") (pintype "power_in"))
      (node (ref "BUCK_6-36V_TO_5V") (pin "5") (pinfunction "PGND_3_5") (pintype "power_in"))
      (node (ref "BUCK_6-36V_TO_5V") (pin "7") (pinfunction "PGND_4_7") (pintype "power_in"))
      (node (ref "BUCK_6-36V_TO_5V") (pin "8") (pinfunction "PGND_8") (pintype "power_in"))
      (node (ref "C1") (pin "1") (pinfunction "1_1") (pintype "passive"))
      (node (ref "C10") (pin "1") (pinfunction "1_1") (pintype "passive"))
      (node (ref "C11") (pin "1") (pinfunction "1_1") (pintype "passive"))
      (node (ref "C12") (pin "1") (pinfunction "1_1") (pintype "passive"))
      (node (ref "C13") (pin "2") (pinfunction "2_2") (pintype "passive"))
      (node (ref "C14") (pin "2") (pinfunction "2_2") (pintype "passive"))
      (node (ref "C15") (pin "2") (pinfunction "2_2") (pintype "passive"))
      (node (ref "C2") (pin "1") (pinfunction "1_1") (pintype "passive"))
      (node (ref "C3") (pin "1") (pinfunction "1_1") (pintype "passive"))
      (node (ref "C4") (pin "1") (pinfunction "1_1") (pintype "passive"))
      (node (ref "C5") (pin "1") (pinfunction "1_1") (pintype "passive"))
      (node (ref "C6") (pin "1") (pinfunction "1_1") (pintype "passive"))
      (node (ref "C7") (pin "1") (pinfunction "1_1") (pintype "passive"))
      (node (ref "C8") (pin "1") (pinfunction "1_1") (pintype "passive"))
      (node (ref "C9") (pin "1") (pinfunction "1_1") (pintype "passive"))
      (node (ref "GNSS") (pin "1") (pinfunction "1_1") (pintype "passive"))
      (node (ref "IMU_JUMPER") (pin "06") (pinfunction "06_06") (pintype "passive"))
      (node (ref "M1") (pin "1") (pinfunction "S_1") (pintype "passive"))
      (node (ref "M1") (pin "2") (pinfunction "S_2") (pintype "passive"))
      (node (ref "M1") (pin "3") (pinfunction "S_3") (pintype "passive"))
      (node (ref "M2") (pin "1") (pinfunction "S_1") (pintype "passive"))
      (node (ref "M2") (pin "2") (pinfunction "S_2") (pintype "passive"))
      (node (ref "M2") (pin "3") (pinfunction "S_3") (pintype "passive"))
      (node (ref "M3") (pin "1") (pinfunction "S_1") (pintype "passive"))
      (node (ref "M3") (pin "2") (pinfunction "S_2") (pintype "passive"))
      (node (ref "M3") (pin "3") (pinfunction "S_3") (pintype "passive"))
      (node (ref "M4") (pin "1") (pinfunction "S_1") (pintype "passive"))
      (node (ref "M4") (pin "2") (pinfunction "S_2") (pintype "passive"))
      (node (ref "M4") (pin "3") (pinfunction "S_3") (pintype "passive"))
      (node (ref "M5") (pin "1") (pinfunction "S_1") (pintype "passive"))
      (node (ref "M5") (pin "2") (pinfunction "S_2") (pintype "passive"))
      (node (ref "M5") (pin "3") (pinfunction "S_3") (pintype "passive"))
      (node (ref "OPENIMU300ZI") (pin "13A") (pinfunction "13_13A") (pintype "bidirectional"))
      (node (ref "OPENIMU300ZI") (pin "14A") (pinfunction "14_14A") (pintype "bidirectional"))
      (node (ref "OPENIMU300ZI") (pin "15A") (pinfunction "15_15A") (pintype "bidirectional"))
      (node (ref "R11") (pin "1") (pinfunction "1_1") (pintype "passive"))
      (node (ref "R13") (pin "1") (pinfunction "1_1") (pintype "passive"))
      (node (ref "R15") (pin "1") (pinfunction "1_1") (pintype "passive"))
      (node (ref "R17") (pin "1") (pinfunction "1_1") (pintype "passive"))
      (node (ref "R19") (pin "1") (pinfunction "1_1") (pintype "passive"))
      (node (ref "R21") (pin "1") (pinfunction "1_1") (pintype "passive"))
      (node (ref "R27") (pin "2") (pinfunction "2_2") (pintype "passive"))
      (node (ref "R33") (pin "1") (pinfunction "1_1") (pintype "passive"))
      (node (ref "R7") (pin "1") (pinfunction "1_1") (pintype "passive"))
      (node (ref "R9") (pin "1") (pinfunction "1_1") (pintype "passive"))
      (node (ref "RPI_16P") (pin "14") (pinfunction "14_14") (pintype "passive"))
      (node (ref "RPI_16P") (pin "6") (pinfunction "6_6") (pintype "passive"))
      (node (ref "RPI_16P") (pin "9") (pinfunction "9_9") (pintype "passive"))
      (node (ref "S1,2") (pin "1") (pinfunction "1_1") (pintype "passive"))
      (node (ref "S1,2") (pin "4") (pinfunction "4_4") (pintype "passive"))
      (node (ref "S11,12") (pin "1") (pinfunction "1_1") (pintype "passive"))
      (node (ref "S11,12") (pin "4") (pinfunction "4_4") (pintype "passive"))
      (node (ref "S3,4") (pin "1") (pinfunction "1_1") (pintype "passive"))
      (node (ref "S3,4") (pin "4") (pinfunction "4_4") (pintype "passive"))
      (node (ref "S5,6") (pin "1") (pinfunction "1_1") (pintype "passive"))
      (node (ref "S5,6") (pin "4") (pinfunction "4_4") (pintype "passive"))
      (node (ref "S7,8") (pin "1") (pinfunction "1_1") (pintype "passive"))
      (node (ref "S7,8") (pin "4") (pinfunction "4_4") (pintype "passive"))
      (node (ref "S9,10") (pin "1") (pinfunction "1_1") (pintype "passive"))
      (node (ref "S9,10") (pin "4") (pinfunction "4_4") (pintype "passive"))
      (node (ref "SPI1") (pin "2") (pinfunction "2_2") (pintype "passive"))
      (node (ref "T4.1L") (pin "1") (pinfunction "1_1") (pintype "passive"))
      (node (ref "T4.1L") (pin "2") (pinfunction "2_2") (pintype "passive"))
      (node (ref "T4.1R") (pin "29") (pinfunction "29_29") (pintype "passive"))
      (node (ref "T4.1R") (pin "3") (pinfunction "3_3") (pintype "passive"))
      (node (ref "T4.1R") (pin "30") (pinfunction "30_30") (pintype "passive"))
      (node (ref "T4.1R") (pin "4") (pinfunction "4_4") (pintype "passive"))
      (node (ref "WIRE") (pin "1") (pinfunction "1_1") (pintype "power_in"))
      (node (ref "WIRE1") (pin "1") (pinfunction "1_1") (pintype "power_in"))
      (node (ref "WIRE2_AND_PIWIRE") (pin "1") (pinfunction "1_1") (pintype "power_in"))
    )
    (net (code "46") (name "IMU3-TX-SCK") (class "Default")
      (node (ref "IMU_IN") (pin "4") (pinfunction "4_4") (pintype "passive"))
      (node (ref "OPENIMU300ZI") (pin "3A") (pinfunction "3_3A") (pintype "bidirectional"))
    )
    (net (code "47") (name "IMU4-RX-MISO") (class "Default")
      (node (ref "IMU_IN") (pin "3") (pinfunction "3_3") (pintype "passive"))
      (node (ref "OPENIMU300ZI") (pin "4A") (pinfunction "4_4A") (pintype "bidirectional"))
    )
    (net (code "48") (name "IMU5-TX1-MOSI") (class "Default")
      (node (ref "IMU_IN") (pin "2") (pinfunction "2_2") (pintype "power_in"))
      (node (ref "OPENIMU300ZI") (pin "5A") (pinfunction "5_5A") (pintype "bidirectional"))
    )
    (net (code "49") (name "IMU6-RX1-CS") (class "Default")
      (node (ref "IMU_IN") (pin "1") (pinfunction "1_1") (pintype "power_in"))
      (node (ref "OPENIMU300ZI") (pin "6A") (pinfunction "6_6A") (pintype "bidirectional"))
    )
    (net (code "50") (name "IMU7-UART{slash}SPI-SEL") (class "Default")
      (node (ref "IMU_JUMPER") (pin "04") (pinfunction "04_04") (pintype "passive"))
      (node (ref "OPENIMU300ZI") (pin "7A") (pinfunction "7_7A") (pintype "bidirectional"))
    )
    (net (code "51") (name "IMU16-SWDIO") (class "Default")
      (node (ref "IMU_JUMPER") (pin "01") (pinfunction "01_01") (pintype "passive"))
      (node (ref "OPENIMU300ZI") (pin "16A") (pinfunction "16_16A") (pintype "bidirectional"))
    )
    (net (code "52") (name "IMU17-TX2") (class "Default")
      (node (ref "GNSS") (pin "5") (pinfunction "5_5") (pintype "passive"))
      (node (ref "OPENIMU300ZI") (pin "17A") (pinfunction "17_17A") (pintype "bidirectional"))
    )
    (net (code "53") (name "IMU18-SWCLK") (class "Default")
      (node (ref "IMU_JUMPER") (pin "03") (pinfunction "03_03") (pintype "passive"))
      (node (ref "OPENIMU300ZI") (pin "18A") (pinfunction "18_18A") (pintype "bidirectional"))
    )
    (net (code "54") (name "IMU19-RX2") (class "Default")
      (node (ref "GNSS") (pin "6") (pinfunction "6_6") (pintype "passive"))
      (node (ref "OPENIMU300ZI") (pin "19A") (pinfunction "19_19A") (pintype "bidirectional"))
    )
    (net (code "55") (name "IMU20-VREF_SWD") (class "Default")
      (node (ref "IMU_JUMPER") (pin "05") (pinfunction "05_05") (pintype "passive"))
      (node (ref "OPENIMU300ZI") (pin "20A") (pinfunction "20_20A") (pintype "bidirectional"))
    )
    (net (code "56") (name "Net-(BUCK_6-36V_TO_5V-BIAS)") (class "Default")
      (node (ref "BUCK_6-36V_TO_5V") (pin "13") (pinfunction "BIAS_13") (pintype "output"))
      (node (ref "BUCK_6-36V_TO_5V") (pin "16") (pinfunction "FB_16") (pintype "input"))
      (node (ref "C15") (pin "1") (pinfunction "1_1") (pintype "passive"))
    )
    (net (code "57") (name "Net-(BUCK_6-36V_TO_5V-BST)") (class "Default")
      (node (ref "BUCK_6-36V_TO_5V") (pin "3") (pinfunction "BST_3") (pintype "passive"))
      (node (ref "C16") (pin "2") (pinfunction "2_2") (pintype "passive"))
    )
    (net (code "58") (name "Net-(BUCK_6-36V_TO_5V-COMP)") (class "Default")
      (node (ref "BUCK_6-36V_TO_5V") (pin "15") (pinfunction "COMP_15") (pintype "output"))
      (node (ref "C12") (pin "2") (pinfunction "2_2") (pintype "passive"))
      (node (ref "R28") (pin "2") (pinfunction "2_2") (pintype "passive"))
    )
    (net (code "59") (name "Net-(BUCK_6-36V_TO_5V-FOSC)") (class "Default")
      (node (ref "BUCK_6-36V_TO_5V") (pin "17") (pinfunction "FOSC_17") (pintype "input"))
      (node (ref "R25") (pin "1") (pinfunction "1_1") (pintype "passive"))
    )
    (net (code "60") (name "Net-(BUCK_6-36V_TO_5V-LX)") (class "Default")
      (node (ref "BUCK_6-36V_TO_5V") (pin "6") (pinfunction "LX_6") (pintype "passive"))
      (node (ref "C16") (pin "1") (pinfunction "1_1") (pintype "passive"))
      (node (ref "L1-1UH") (pin "2") (pinfunction "2_2") (pintype "passive"))
    )
    (net (code "61") (name "Net-(BUCK_6-36V_TO_5V-~{RESET})") (class "Default")
      (node (ref "BUCK_6-36V_TO_5V") (pin "2") (pinfunction "~{RESET}_2") (pintype "output"))
      (node (ref "R23") (pin "2") (pinfunction "2_2") (pintype "passive"))
    )
    (net (code "62") (name "Net-(C11-Pad2)") (class "Default")
      (node (ref "C11") (pin "2") (pinfunction "2_2") (pintype "passive"))
      (node (ref "R31") (pin "1") (pinfunction "1_1") (pintype "passive"))
    )
    (net (code "63") (name "Net-(M1-D)") (class "Default")
      (node (ref "M1") (pin "5") (pinfunction "D_5") (pintype "passive"))
      (node (ref "P1") (pin "2") (pinfunction "2_2") (pintype "passive"))
      (node (ref "R10") (pin "2") (pinfunction "2_2") (pintype "passive"))
    )
    (net (code "64") (name "Net-(M1-G)") (class "Default")
      (node (ref "M1") (pin "4") (pinfunction "G_4") (pintype "passive"))
      (node (ref "R8") (pin "2") (pinfunction "2_2") (pintype "passive"))
    )
    (net (code "65") (name "Net-(M2-D)") (class "Default")
      (node (ref "M2") (pin "5") (pinfunction "D_5") (pintype "passive"))
      (node (ref "P2") (pin "2") (pinfunction "2_2") (pintype "passive"))
      (node (ref "R14") (pin "2") (pinfunction "2_2") (pintype "passive"))
    )
    (net (code "66") (name "Net-(M2-G)") (class "Default")
      (node (ref "M2") (pin "4") (pinfunction "G_4") (pintype "passive"))
      (node (ref "R12") (pin "2") (pinfunction "2_2") (pintype "passive"))
    )
    (net (code "67") (name "Net-(M3-D)") (class "Default")
      (node (ref "M3") (pin "5") (pinfunction "D_5") (pintype "passive"))
      (node (ref "P3") (pin "2") (pinfunction "2_2") (pintype "passive"))
      (node (ref "R18") (pin "2") (pinfunction "2_2") (pintype "passive"))
    )
    (net (code "68") (name "Net-(M3-G)") (class "Default")
      (node (ref "M3") (pin "4") (pinfunction "G_4") (pintype "passive"))
      (node (ref "R16") (pin "2") (pinfunction "2_2") (pintype "passive"))
    )
    (net (code "69") (name "Net-(M4-D)") (class "Default")
      (node (ref "M4") (pin "5") (pinfunction "D_5") (pintype "passive"))
      (node (ref "P4") (pin "2") (pinfunction "2_2") (pintype "passive"))
    )
    (net (code "70") (name "Net-(M4-G)") (class "Default")
      (node (ref "M4") (pin "4") (pinfunction "G_4") (pintype "passive"))
      (node (ref "R20") (pin "2") (pinfunction "2_2") (pintype "passive"))
    )
    (net (code "71") (name "Net-(M5-D)") (class "Default")
      (node (ref "M5") (pin "5") (pinfunction "D_5") (pintype "passive"))
      (node (ref "P5") (pin "2") (pinfunction "2_2") (pintype "passive"))
    )
    (net (code "72") (name "Net-(M5-G)") (class "Default")
      (node (ref "M5") (pin "4") (pinfunction "G_4") (pintype "passive"))
      (node (ref "R22") (pin "2") (pinfunction "2_2") (pintype "passive"))
    )
    (net (code "73") (name "Net-(R23-Pad1)") (class "Default")
      (node (ref "R23") (pin "1") (pinfunction "1_1") (pintype "passive"))
      (node (ref "R24") (pin "2") (pinfunction "2_2") (pintype "passive"))
    )
    (net (code "74") (name "Net-(R25-Pad2)") (class "Default")
      (node (ref "R25") (pin "2") (pinfunction "2_2") (pintype "passive"))
      (node (ref "R26") (pin "1") (pinfunction "1_1") (pintype "passive"))
    )
    (net (code "75") (name "Net-(R26-Pad2)") (class "Default")
      (node (ref "R26") (pin "2") (pinfunction "2_2") (pintype "passive"))
      (node (ref "R27") (pin "1") (pinfunction "1_1") (pintype "passive"))
    )
    (net (code "76") (name "Net-(R28-Pad1)") (class "Default")
      (node (ref "R28") (pin "1") (pinfunction "1_1") (pintype "passive"))
      (node (ref "R29") (pin "2") (pinfunction "2_2") (pintype "passive"))
    )
    (net (code "77") (name "Net-(R29-Pad1)") (class "Default")
      (node (ref "R29") (pin "1") (pinfunction "1_1") (pintype "passive"))
      (node (ref "R30") (pin "2") (pinfunction "2_2") (pintype "passive"))
    )
    (net (code "78") (name "Net-(R30-Pad1)") (class "Default")
      (node (ref "R30") (pin "1") (pinfunction "1_1") (pintype "passive"))
      (node (ref "R31") (pin "2") (pinfunction "2_2") (pintype "passive"))
    )
    (net (code "79") (name "VCC_1") (class "Default")
      (node (ref "B1_IN") (pin "1") (pinfunction "1_1") (pintype "passive"))
      (node (ref "B1_OUT") (pin "1") (pinfunction "1_1") (pintype "passive"))
      (node (ref "BUCK_6-36V_TO_5V") (pin "10") (pinfunction "SUP_10") (pintype "input"))
      (node (ref "BUCK_6-36V_TO_5V") (pin "11") (pinfunction "EN_11") (pintype "input"))
      (node (ref "BUCK_6-36V_TO_5V") (pin "9") (pinfunction "SUPSW_9") (pintype "input"))
      (node (ref "C13") (pin "1") (pinfunction "1_1") (pintype "passive"))
      (node (ref "C14") (pin "1") (pinfunction "1_1") (pintype "passive"))
      (node (ref "R32") (pin "2") (pinfunction "2_2") (pintype "passive"))
    )
    (net (code "80") (name "VCC_2") (class "Default")
      (node (ref "B2_IN") (pin "1") (pinfunction "1_1") (pintype "passive"))
      (node (ref "P1") (pin "1") (pinfunction "1_1") (pintype "passive"))
      (node (ref "P2") (pin "1") (pinfunction "1_1") (pintype "passive"))
      (node (ref "P3") (pin "1") (pinfunction "1_1") (pintype "passive"))
      (node (ref "P4") (pin "1") (pinfunction "1_1") (pintype "passive"))
      (node (ref "S11,12") (pin "2") (pinfunction "2_2") (pintype "passive"))
      (node (ref "S11,12") (pin "5") (pinfunction "5_5") (pintype "passive"))
      (node (ref "S9,10") (pin "2") (pinfunction "2_2") (pintype "passive"))
      (node (ref "S9,10") (pin "5") (pinfunction "5_5") (pintype "passive"))
    )
    (net (code "81") (name "unconnected-(OPENIMU300ZI-1-Pad1A)") (class "Default")
      (node (ref "OPENIMU300ZI") (pin "1A") (pinfunction "1_1A") (pintype "bidirectional"))
    )
    (net (code "82") (name "unconnected-(OPENIMU300ZI-2-Pad2A)") (class "Default")
      (node (ref "OPENIMU300ZI") (pin "2A") (pinfunction "2_2A") (pintype "bidirectional"))
    )
    (net (code "83") (name "unconnected-(OPENIMU300ZI-9-Pad9A)") (class "Default")
      (node (ref "OPENIMU300ZI") (pin "9A") (pinfunction "9_9A") (pintype "bidirectional"))
    )
    (net (code "84") (name "unconnected-(RPI_16P-Pad1)") (class "Default")
      (node (ref "RPI_16P") (pin "1") (pinfunction "1_1") (pintype "passive"))
    )
    (net (code "85") (name "unconnected-(RPI_16P-Pad7)") (class "Default")
      (node (ref "RPI_16P") (pin "7") (pinfunction "7_7") (pintype "passive"))
    )
    (net (code "86") (name "unconnected-(RPI_16P-Pad11)") (class "Default")
      (node (ref "RPI_16P") (pin "11") (pinfunction "11_11") (pintype "passive"))
    )
    (net (code "87") (name "unconnected-(RPI_16P-Pad12)") (class "Default")
      (node (ref "RPI_16P") (pin "12") (pinfunction "12_12") (pintype "passive"))
    )
    (net (code "88") (name "unconnected-(RPI_16P-Pad13)") (class "Default")
      (node (ref "RPI_16P") (pin "13") (pinfunction "13_13") (pintype "passive"))
    )
    (net (code "89") (name "unconnected-(RPI_16P-Pad15)") (class "Default")
      (node (ref "RPI_16P") (pin "15") (pinfunction "15_15") (pintype "passive"))
    )
    (net (code "90") (name "unconnected-(RPI_16P-Pad16)") (class "Default")
      (node (ref "RPI_16P") (pin "16") (pinfunction "16_16") (pintype "passive"))
    )
  )
)
